# WhetherTime.net
KiCad netlist of a schematic drawn in Altium Designer
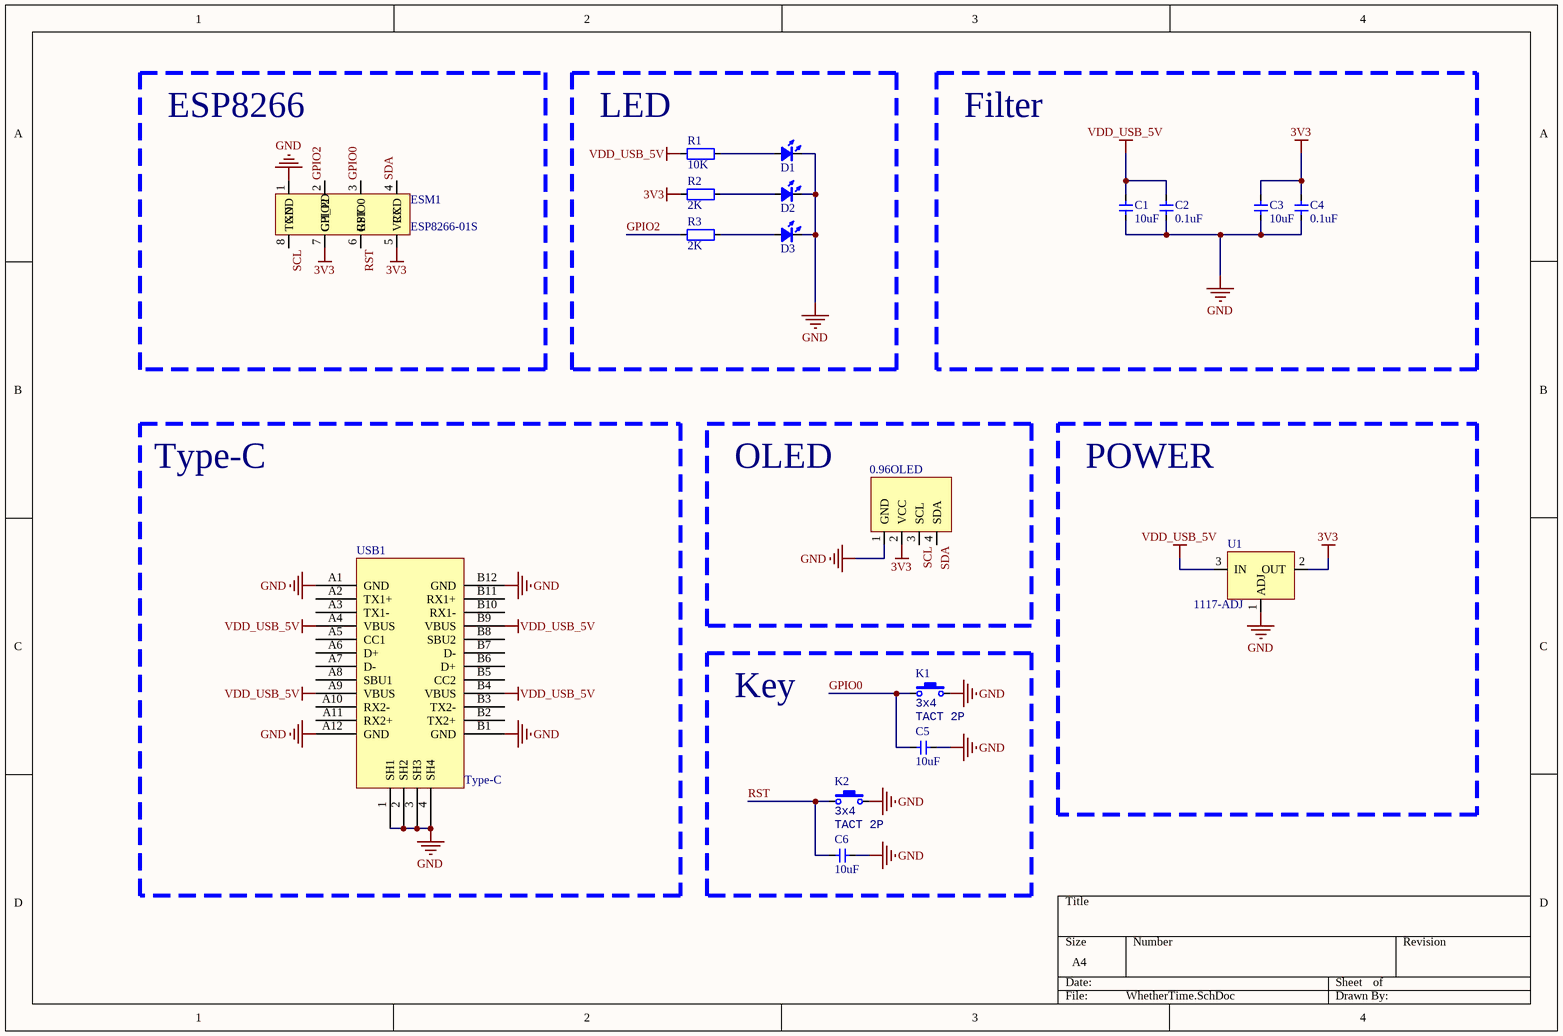
[diagram p0: WhetherTime.SchDoc]

(export (version "E")
  (design (tool "Eeschema 10.0.6"))
  (components
    (comp (ref "*1")
      (value "0.96OLED")
      (footprint "0.96OLED_4P")
      (libsource (lib "WhetherTime") (part "0.96OLED"))
    )
    (comp (ref "C1")
      (value "10uF")
      (footprint "0603-CAP")
      (description "Capacitor")
      (libsource (lib "WhetherTime") (part "电容-0603"))
    )
    (comp (ref "C2")
      (value "0.1uF")
      (footprint "0603-CAP")
      (description "Capacitor")
      (libsource (lib "WhetherTime") (part "电容-0603"))
    )
    (comp (ref "C3")
      (value "10uF")
      (footprint "0603-CAP")
      (description "Capacitor")
      (libsource (lib "WhetherTime") (part "电容-0603"))
    )
    (comp (ref "C4")
      (value "0.1uF")
      (footprint "0603-CAP")
      (description "Capacitor")
      (libsource (lib "WhetherTime") (part "电容-0603"))
    )
    (comp (ref "C5")
      (value "10uF")
      (footprint "0603-CAP")
      (description "Capacitor")
      (libsource (lib "WhetherTime") (part "电容-0603"))
    )
    (comp (ref "C6")
      (value "10uF")
      (footprint "0603-CAP")
      (description "Capacitor")
      (libsource (lib "WhetherTime") (part "电容-0603"))
    )
    (comp (ref "D1")
      (value "color?")
      (footprint "LED_0402")
      (description "LED")
      (libsource (lib "WhetherTime") (part "LED_0603"))
    )
    (comp (ref "D2")
      (value "color?")
      (footprint "LED_0402")
      (description "LED")
      (libsource (lib "WhetherTime") (part "LED_0603"))
    )
    (comp (ref "D3")
      (value "color?")
      (footprint "LED_0402")
      (description "LED")
      (libsource (lib "WhetherTime") (part "LED_0603"))
    )
    (comp (ref "ESM1")
      (value "ESP8266-01S")
      (footprint "ESP8266-01S")
      (libsource (lib "WhetherTime") (part "ESP8266-01S"))
    )
    (comp (ref "K1")
      (value "3x4")
      (footprint "ButtonTACT_3x4x2_180")
      (description "Button")
      (fields (field (name "TYPE") "TACT 2P") (field (name "Comment") "TACT 2P"))
      (libsource (lib "WhetherTime") (part "ButtonTACT_3x4x2_180"))
    )
    (comp (ref "K2")
      (value "3x4")
      (footprint "ButtonTACT_3x4x2_180")
      (description "Button")
      (fields (field (name "TYPE") "TACT 2P") (field (name "Comment") "TACT 2P"))
      (libsource (lib "WhetherTime") (part "ButtonTACT_3x4x2_180"))
    )
    (comp (ref "R1")
      (value "10K")
      (footprint "0603-RES")
      (description "Resistor")
      (libsource (lib "WhetherTime") (part "电阻-0603"))
    )
    (comp (ref "R2")
      (value "2K")
      (footprint "0603-RES")
      (description "Resistor")
      (libsource (lib "WhetherTime") (part "电阻-0603"))
    )
    (comp (ref "R3")
      (value "2K")
      (footprint "0603-RES")
      (description "Resistor")
      (libsource (lib "WhetherTime") (part "电阻-0603"))
    )
    (comp (ref "U1")
      (value "1117-ADJ")
      (footprint "SOT223_JX")
      (description "IC")
      (libsource (lib "WhetherTime") (part "AMS1117-ADJ"))
    )
    (comp (ref "USB1")
      (value "Type-C")
      (footprint "Type-C-TOP")
      (libsource (lib "WhetherTime") (part "USB-Type-C-TOP"))
    )
  )
  (nets
    (net (code "1") (name "/GPIO0") (class "Default")
      (node (ref "C5") (pin "2") (pinfunction "2_2") (pintype "passive"))
      (node (ref "ESM1") (pin "3") (pinfunction "GPIO0_3") (pintype "passive"))
      (node (ref "K1") (pin "1") (pinfunction "1_1") (pintype "passive"))
    )
    (net (code "2") (name "/GPIO2") (class "Default")
      (node (ref "ESM1") (pin "2") (pinfunction "GPIO2_2") (pintype "passive"))
      (node (ref "R3") (pin "1") (pinfunction "1_1") (pintype "passive"))
    )
    (net (code "3") (name "/RST") (class "Default")
      (node (ref "C6") (pin "2") (pinfunction "2_2") (pintype "passive"))
      (node (ref "ESM1") (pin "6") (pinfunction "RST_6") (pintype "passive"))
      (node (ref "K2") (pin "1") (pinfunction "1_1") (pintype "passive"))
    )
    (net (code "4") (name "/SCL") (class "Default")
      (node (ref "*1") (pin "3") (pinfunction "SCL_3") (pintype "passive"))
      (node (ref "ESM1") (pin "8") (pinfunction "TXD_8") (pintype "passive"))
    )
    (net (code "5") (name "/SDA") (class "Default")
      (node (ref "*1") (pin "4") (pinfunction "SDA_4") (pintype "passive"))
      (node (ref "ESM1") (pin "4") (pinfunction "RXD_4") (pintype "passive"))
    )
    (net (code "6") (name "3V3") (class "Default")
      (node (ref "*1") (pin "2") (pinfunction "VCC_2") (pintype "passive"))
      (node (ref "C3") (pin "2") (pinfunction "2_2") (pintype "passive"))
      (node (ref "C4") (pin "2") (pinfunction "2_2") (pintype "passive"))
      (node (ref "ESM1") (pin "5") (pinfunction "VCC_5") (pintype "passive"))
      (node (ref "ESM1") (pin "7") (pinfunction "CH_PD_7") (pintype "passive"))
      (node (ref "R2") (pin "1") (pinfunction "1_1") (pintype "passive"))
      (node (ref "U1") (pin "2") (pinfunction "OUT_2") (pintype "passive"))
    )
    (net (code "7") (name "GND") (class "Default")
      (node (ref "*1") (pin "1") (pinfunction "GND_1") (pintype "passive"))
      (node (ref "C1") (pin "1") (pinfunction "1_1") (pintype "passive"))
      (node (ref "C2") (pin "1") (pinfunction "1_1") (pintype "passive"))
      (node (ref "C3") (pin "1") (pinfunction "1_1") (pintype "passive"))
      (node (ref "C4") (pin "1") (pinfunction "1_1") (pintype "passive"))
      (node (ref "C5") (pin "1") (pinfunction "1_1") (pintype "passive"))
      (node (ref "C6") (pin "1") (pinfunction "1_1") (pintype "passive"))
      (node (ref "D1") (pin "2") (pinfunction "K_2") (pintype "passive"))
      (node (ref "D2") (pin "2") (pinfunction "K_2") (pintype "passive"))
      (node (ref "D3") (pin "2") (pinfunction "K_2") (pintype "passive"))
      (node (ref "ESM1") (pin "1") (pinfunction "GND_1") (pintype "passive"))
      (node (ref "K1") (pin "2") (pinfunction "2_2") (pintype "passive"))
      (node (ref "K2") (pin "2") (pinfunction "2_2") (pintype "passive"))
      (node (ref "U1") (pin "1") (pinfunction "ADJ_1") (pintype "passive"))
      (node (ref "USB1") (pin "1") (pinfunction "SH1_1") (pintype "passive"))
      (node (ref "USB1") (pin "2") (pinfunction "SH2_2") (pintype "passive"))
      (node (ref "USB1") (pin "3") (pinfunction "SH3_3") (pintype "passive"))
      (node (ref "USB1") (pin "4") (pinfunction "SH4_4") (pintype "passive"))
      (node (ref "USB1") (pin "A1") (pinfunction "GND_A1") (pintype "passive"))
      (node (ref "USB1") (pin "A12") (pinfunction "GND_A12") (pintype "passive"))
      (node (ref "USB1") (pin "B1") (pinfunction "GND_B1") (pintype "passive"))
      (node (ref "USB1") (pin "B12") (pinfunction "GND_B12") (pintype "passive"))
    )
    (net (code "8") (name "Net-(D1-A)") (class "Default")
      (node (ref "D1") (pin "1") (pinfunction "A_1") (pintype "passive"))
      (node (ref "R1") (pin "2") (pinfunction "2_2") (pintype "passive"))
    )
    (net (code "9") (name "Net-(D2-A)") (class "Default")
      (node (ref "D2") (pin "1") (pinfunction "A_1") (pintype "passive"))
      (node (ref "R2") (pin "2") (pinfunction "2_2") (pintype "passive"))
    )
    (net (code "10") (name "Net-(D3-A)") (class "Default")
      (node (ref "D3") (pin "1") (pinfunction "A_1") (pintype "passive"))
      (node (ref "R3") (pin "2") (pinfunction "2_2") (pintype "passive"))
    )
    (net (code "11") (name "VDD_USB_5V") (class "Default")
      (node (ref "C1") (pin "2") (pinfunction "2_2") (pintype "passive"))
      (node (ref "C2") (pin "2") (pinfunction "2_2") (pintype "passive"))
      (node (ref "R1") (pin "1") (pinfunction "1_1") (pintype "passive"))
      (node (ref "U1") (pin "3") (pinfunction "IN_3") (pintype "passive"))
      (node (ref "USB1") (pin "A4") (pinfunction "VBUS_A4") (pintype "passive"))
      (node (ref "USB1") (pin "A9") (pinfunction "VBUS_A9") (pintype "passive"))
      (node (ref "USB1") (pin "B4") (pinfunction "VBUS_B4") (pintype "passive"))
      (node (ref "USB1") (pin "B9") (pinfunction "VBUS_B9") (pintype "passive"))
    )
    (net (code "12") (name "unconnected-(USB1-CC1-PadA5)") (class "Default")
      (node (ref "USB1") (pin "A5") (pinfunction "CC1_A5") (pintype "passive"))
    )
    (net (code "13") (name "unconnected-(USB1-CC2-PadB5)") (class "Default")
      (node (ref "USB1") (pin "B5") (pinfunction "CC2_B5") (pintype "passive"))
    )
    (net (code "14") (name "unconnected-(USB1-D+-PadA6)") (class "Default")
      (node (ref "USB1") (pin "A6") (pinfunction "D+_A6") (pintype "passive"))
    )
    (net (code "15") (name "unconnected-(USB1-D+-PadB6)") (class "Default")
      (node (ref "USB1") (pin "B6") (pinfunction "D+_B6") (pintype "passive"))
    )
    (net (code "16") (name "unconnected-(USB1-D--PadA7)") (class "Default")
      (node (ref "USB1") (pin "A7") (pinfunction "D-_A7") (pintype "passive"))
    )
    (net (code "17") (name "unconnected-(USB1-D--PadB7)") (class "Default")
      (node (ref "USB1") (pin "B7") (pinfunction "D-_B7") (pintype "passive"))
    )
    (net (code "18") (name "unconnected-(USB1-RX1+-PadB11)") (class "Default")
      (node (ref "USB1") (pin "B11") (pinfunction "RX1+_B11") (pintype "passive"))
    )
    (net (code "19") (name "unconnected-(USB1-RX1--PadB10)") (class "Default")
      (node (ref "USB1") (pin "B10") (pinfunction "RX1-_B10") (pintype "passive"))
    )
    (net (code "20") (name "unconnected-(USB1-RX2+-PadA11)") (class "Default")
      (node (ref "USB1") (pin "A11") (pinfunction "RX2+_A11") (pintype "passive"))
    )
    (net (code "21") (name "unconnected-(USB1-RX2--PadA10)") (class "Default")
      (node (ref "USB1") (pin "A10") (pinfunction "RX2-_A10") (pintype "passive"))
    )
    (net (code "22") (name "unconnected-(USB1-SBU1-PadA8)") (class "Default")
      (node (ref "USB1") (pin "A8") (pinfunction "SBU1_A8") (pintype "passive"))
    )
    (net (code "23") (name "unconnected-(USB1-SBU2-PadB8)") (class "Default")
      (node (ref "USB1") (pin "B8") (pinfunction "SBU2_B8") (pintype "passive"))
    )
    (net (code "24") (name "unconnected-(USB1-TX1+-PadA2)") (class "Default")
      (node (ref "USB1") (pin "A2") (pinfunction "TX1+_A2") (pintype "passive"))
    )
    (net (code "25") (name "unconnected-(USB1-TX1--PadA3)") (class "Default")
      (node (ref "USB1") (pin "A3") (pinfunction "TX1-_A3") (pintype "passive"))
    )
    (net (code "26") (name "unconnected-(USB1-TX2+-PadB2)") (class "Default")
      (node (ref "USB1") (pin "B2") (pinfunction "TX2+_B2") (pintype "passive"))
    )
    (net (code "27") (name "unconnected-(USB1-TX2--PadB3)") (class "Default")
      (node (ref "USB1") (pin "B3") (pinfunction "TX2-_B3") (pintype "passive"))
    )
  )
)
